# v7-flex2811_8x.net
KiCad netlist of a schematic drawn in EAGLE
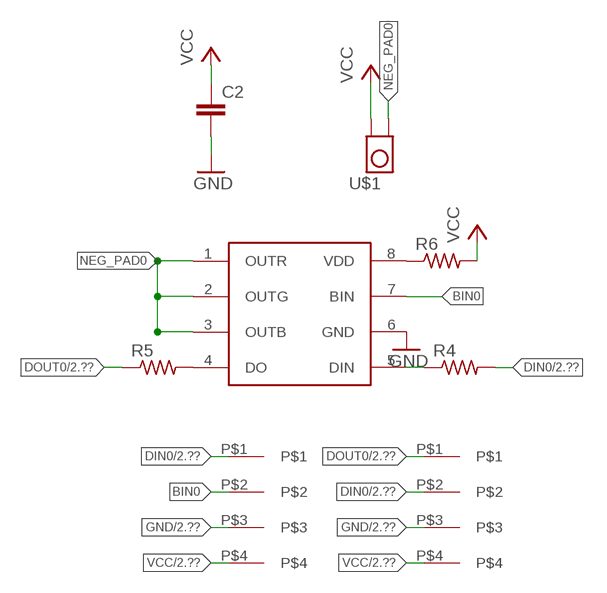
[diagram p0: schematic, sheet 1]
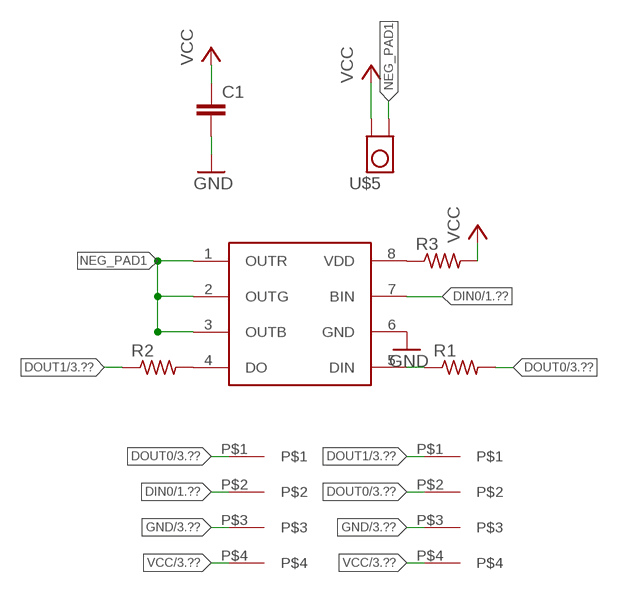
[diagram p1: schematic, sheet 2]
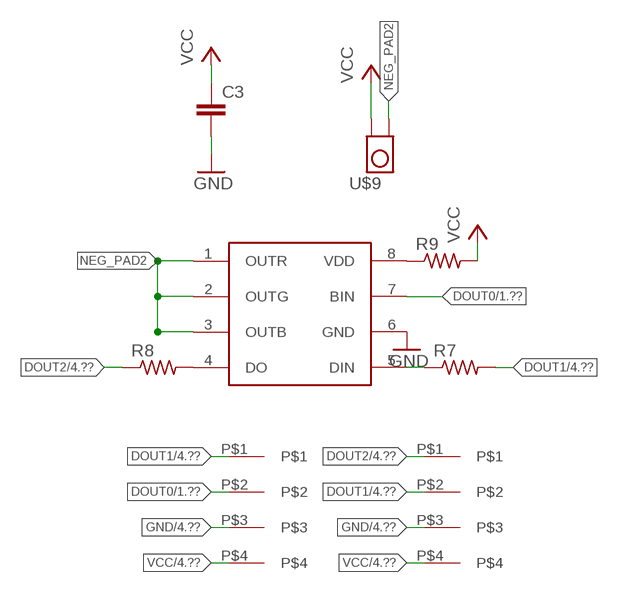
[diagram p2: schematic, sheet 3]
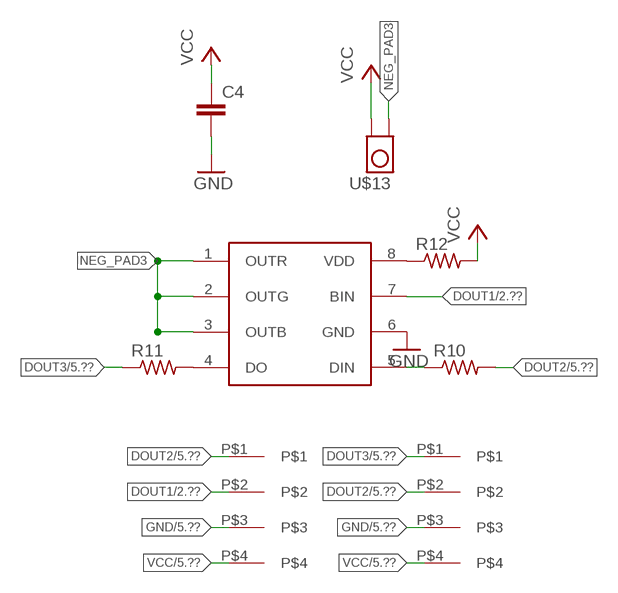
[diagram p3: schematic, sheet 4]
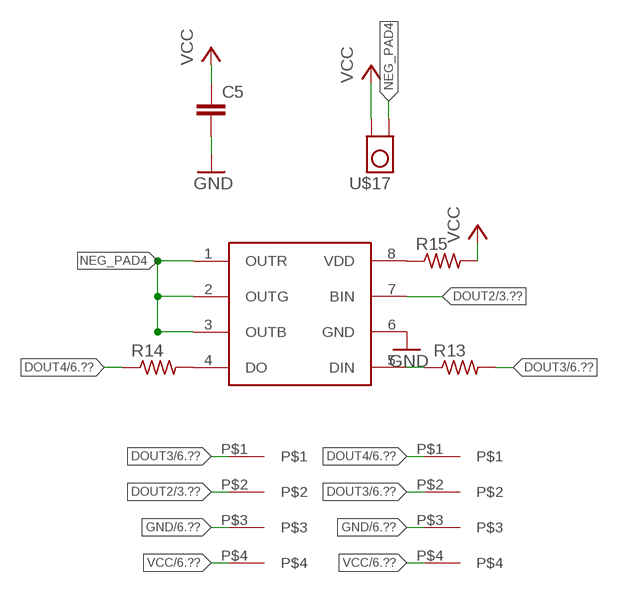
[diagram p4: schematic, sheet 5]
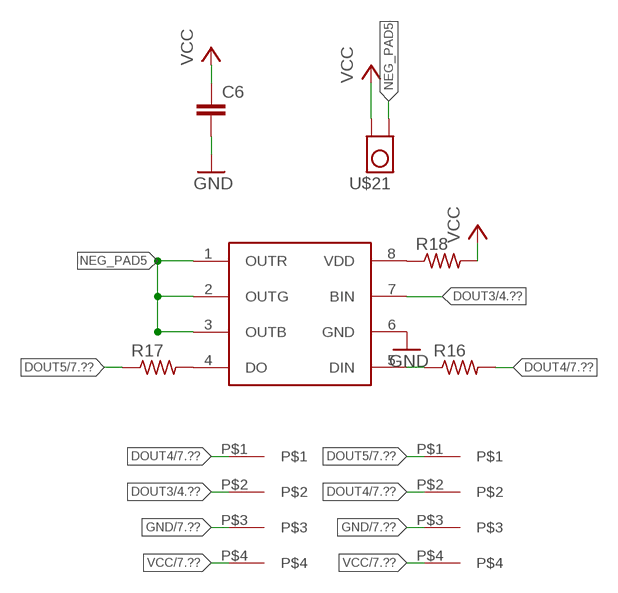
[diagram p5: schematic, sheet 6]
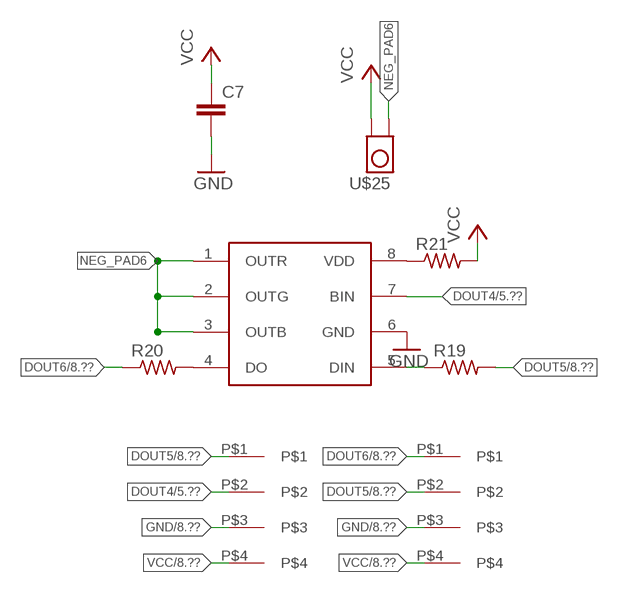
[diagram p6: schematic, sheet 7]
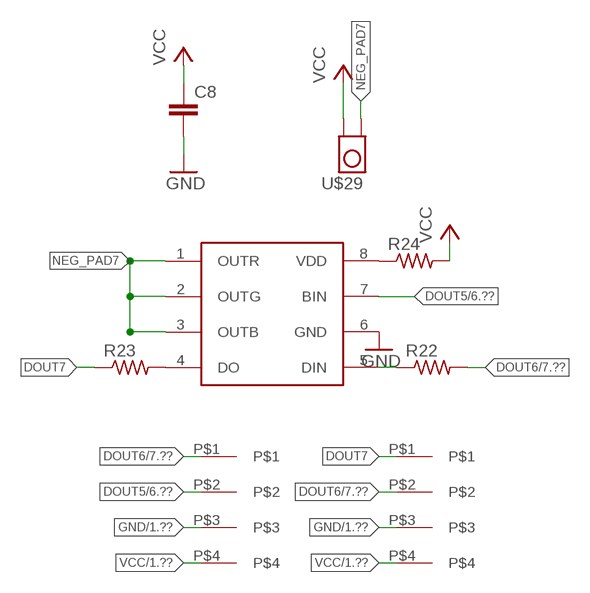
[diagram p7: schematic, sheet 8]

(export (version "E")
  (design (tool "Eeschema 10.0.6"))
  (components
    (comp (ref "C8")
      (value "C-EUC0201")
      (footprint "eagle-import:C0201")
      (libsource (lib "eagle-import") (part "C-EUC0201"))
    )
    (comp (ref "R22")
      (value "R-US_R0201")
      (footprint "eagle-import:R0201")
      (libsource (lib "eagle-import") (part "R-US_R0201"))
    )
    (comp (ref "R23")
      (value "R-US_R0201")
      (footprint "eagle-import:R0201")
      (libsource (lib "eagle-import") (part "R-US_R0201"))
    )
    (comp (ref "R24")
      (value "R-US_R0201")
      (footprint "eagle-import:R0201")
      (libsource (lib "eagle-import") (part "R-US_R0201"))
    )
    (comp (ref "U$29")
      (value "TP_4MM_MED_PAD")
      (footprint "eagle-import:TP_4MM_MED_PAD")
      (libsource (lib "eagle-import") (part "TP_4MM_MED_PAD"))
    )
    (comp (ref "U$30")
      (value "WS2818")
      (footprint "eagle-import:SO08")
      (libsource (lib "eagle-import") (part "WS2818"))
    )
    (comp (ref "U$31")
      (value "4PAD")
      (footprint "eagle-import:4PAD")
      (libsource (lib "eagle-import") (part "4PAD"))
    )
    (comp (ref "U$32")
      (value "4PAD")
      (footprint "eagle-import:4PAD")
      (libsource (lib "eagle-import") (part "4PAD"))
    )
    (comp (ref "C4")
      (value "C-EUC0201")
      (footprint "eagle-import:C0201")
      (libsource (lib "eagle-import") (part "C-EUC0201"))
    )
    (comp (ref "R10")
      (value "R-US_R0201")
      (footprint "eagle-import:R0201")
      (libsource (lib "eagle-import") (part "R-US_R0201"))
    )
    (comp (ref "R11")
      (value "R-US_R0201")
      (footprint "eagle-import:R0201")
      (libsource (lib "eagle-import") (part "R-US_R0201"))
    )
    (comp (ref "R12")
      (value "R-US_R0201")
      (footprint "eagle-import:R0201")
      (libsource (lib "eagle-import") (part "R-US_R0201"))
    )
    (comp (ref "U$13")
      (value "TP_4MM_MED_PAD")
      (footprint "eagle-import:TP_4MM_MED_PAD")
      (libsource (lib "eagle-import") (part "TP_4MM_MED_PAD"))
    )
    (comp (ref "U$14")
      (value "WS2818")
      (footprint "eagle-import:SO08")
      (libsource (lib "eagle-import") (part "WS2818"))
    )
    (comp (ref "U$15")
      (value "4PAD")
      (footprint "eagle-import:4PAD")
      (libsource (lib "eagle-import") (part "4PAD"))
    )
    (comp (ref "U$16")
      (value "4PAD")
      (footprint "eagle-import:4PAD")
      (libsource (lib "eagle-import") (part "4PAD"))
    )
    (comp (ref "C5")
      (value "C-EUC0201")
      (footprint "eagle-import:C0201")
      (libsource (lib "eagle-import") (part "C-EUC0201"))
    )
    (comp (ref "R13")
      (value "R-US_R0201")
      (footprint "eagle-import:R0201")
      (libsource (lib "eagle-import") (part "R-US_R0201"))
    )
    (comp (ref "R14")
      (value "R-US_R0201")
      (footprint "eagle-import:R0201")
      (libsource (lib "eagle-import") (part "R-US_R0201"))
    )
    (comp (ref "R15")
      (value "R-US_R0201")
      (footprint "eagle-import:R0201")
      (libsource (lib "eagle-import") (part "R-US_R0201"))
    )
    (comp (ref "U$17")
      (value "TP_4MM_MED_PAD")
      (footprint "eagle-import:TP_4MM_MED_PAD")
      (libsource (lib "eagle-import") (part "TP_4MM_MED_PAD"))
    )
    (comp (ref "U$18")
      (value "WS2818")
      (footprint "eagle-import:SO08")
      (libsource (lib "eagle-import") (part "WS2818"))
    )
    (comp (ref "U$19")
      (value "4PAD")
      (footprint "eagle-import:4PAD")
      (libsource (lib "eagle-import") (part "4PAD"))
    )
    (comp (ref "U$20")
      (value "4PAD")
      (footprint "eagle-import:4PAD")
      (libsource (lib "eagle-import") (part "4PAD"))
    )
    (comp (ref "C7")
      (value "C-EUC0201")
      (footprint "eagle-import:C0201")
      (libsource (lib "eagle-import") (part "C-EUC0201"))
    )
    (comp (ref "R19")
      (value "R-US_R0201")
      (footprint "eagle-import:R0201")
      (libsource (lib "eagle-import") (part "R-US_R0201"))
    )
    (comp (ref "R20")
      (value "R-US_R0201")
      (footprint "eagle-import:R0201")
      (libsource (lib "eagle-import") (part "R-US_R0201"))
    )
    (comp (ref "R21")
      (value "R-US_R0201")
      (footprint "eagle-import:R0201")
      (libsource (lib "eagle-import") (part "R-US_R0201"))
    )
    (comp (ref "U$25")
      (value "TP_4MM_MED_PAD")
      (footprint "eagle-import:TP_4MM_MED_PAD")
      (libsource (lib "eagle-import") (part "TP_4MM_MED_PAD"))
    )
    (comp (ref "U$26")
      (value "WS2818")
      (footprint "eagle-import:SO08")
      (libsource (lib "eagle-import") (part "WS2818"))
    )
    (comp (ref "U$27")
      (value "4PAD")
      (footprint "eagle-import:4PAD")
      (libsource (lib "eagle-import") (part "4PAD"))
    )
    (comp (ref "U$28")
      (value "4PAD")
      (footprint "eagle-import:4PAD")
      (libsource (lib "eagle-import") (part "4PAD"))
    )
    (comp (ref "C2")
      (value "C-EUC0201")
      (footprint "eagle-import:C0201")
      (libsource (lib "eagle-import") (part "C-EUC0201"))
    )
    (comp (ref "R4")
      (value "R-US_R0201")
      (footprint "eagle-import:R0201")
      (libsource (lib "eagle-import") (part "R-US_R0201"))
    )
    (comp (ref "R5")
      (value "R-US_R0201")
      (footprint "eagle-import:R0201")
      (libsource (lib "eagle-import") (part "R-US_R0201"))
    )
    (comp (ref "R6")
      (value "R-US_R0201")
      (footprint "eagle-import:R0201")
      (libsource (lib "eagle-import") (part "R-US_R0201"))
    )
    (comp (ref "U$1")
      (value "TP_4MM_MED_PAD")
      (footprint "eagle-import:TP_4MM_MED_PAD")
      (libsource (lib "eagle-import") (part "TP_4MM_MED_PAD"))
    )
    (comp (ref "U$2")
      (value "WS2818")
      (footprint "eagle-import:SO08")
      (libsource (lib "eagle-import") (part "WS2818"))
    )
    (comp (ref "U$3")
      (value "4PAD")
      (footprint "eagle-import:4PAD")
      (libsource (lib "eagle-import") (part "4PAD"))
    )
    (comp (ref "U$4")
      (value "4PAD")
      (footprint "eagle-import:4PAD")
      (libsource (lib "eagle-import") (part "4PAD"))
    )
    (comp (ref "C6")
      (value "C-EUC0201")
      (footprint "eagle-import:C0201")
      (libsource (lib "eagle-import") (part "C-EUC0201"))
    )
    (comp (ref "R16")
      (value "R-US_R0201")
      (footprint "eagle-import:R0201")
      (libsource (lib "eagle-import") (part "R-US_R0201"))
    )
    (comp (ref "R17")
      (value "R-US_R0201")
      (footprint "eagle-import:R0201")
      (libsource (lib "eagle-import") (part "R-US_R0201"))
    )
    (comp (ref "R18")
      (value "R-US_R0201")
      (footprint "eagle-import:R0201")
      (libsource (lib "eagle-import") (part "R-US_R0201"))
    )
    (comp (ref "U$21")
      (value "TP_4MM_MED_PAD")
      (footprint "eagle-import:TP_4MM_MED_PAD")
      (libsource (lib "eagle-import") (part "TP_4MM_MED_PAD"))
    )
    (comp (ref "U$22")
      (value "WS2818")
      (footprint "eagle-import:SO08")
      (libsource (lib "eagle-import") (part "WS2818"))
    )
    (comp (ref "U$23")
      (value "4PAD")
      (footprint "eagle-import:4PAD")
      (libsource (lib "eagle-import") (part "4PAD"))
    )
    (comp (ref "U$24")
      (value "4PAD")
      (footprint "eagle-import:4PAD")
      (libsource (lib "eagle-import") (part "4PAD"))
    )
    (comp (ref "C3")
      (value "C-EUC0201")
      (footprint "eagle-import:C0201")
      (libsource (lib "eagle-import") (part "C-EUC0201"))
    )
    (comp (ref "R7")
      (value "R-US_R0201")
      (footprint "eagle-import:R0201")
      (libsource (lib "eagle-import") (part "R-US_R0201"))
    )
    (comp (ref "R8")
      (value "R-US_R0201")
      (footprint "eagle-import:R0201")
      (libsource (lib "eagle-import") (part "R-US_R0201"))
    )
    (comp (ref "R9")
      (value "R-US_R0201")
      (footprint "eagle-import:R0201")
      (libsource (lib "eagle-import") (part "R-US_R0201"))
    )
    (comp (ref "U$9")
      (value "TP_4MM_MED_PAD")
      (footprint "eagle-import:TP_4MM_MED_PAD")
      (libsource (lib "eagle-import") (part "TP_4MM_MED_PAD"))
    )
    (comp (ref "U$10")
      (value "WS2818")
      (footprint "eagle-import:SO08")
      (libsource (lib "eagle-import") (part "WS2818"))
    )
    (comp (ref "U$11")
      (value "4PAD")
      (footprint "eagle-import:4PAD")
      (libsource (lib "eagle-import") (part "4PAD"))
    )
    (comp (ref "U$12")
      (value "4PAD")
      (footprint "eagle-import:4PAD")
      (libsource (lib "eagle-import") (part "4PAD"))
    )
    (comp (ref "C1")
      (value "C-EUC0201")
      (footprint "eagle-import:C0201")
      (libsource (lib "eagle-import") (part "C-EUC0201"))
    )
    (comp (ref "R1")
      (value "R-US_R0201")
      (footprint "eagle-import:R0201")
      (libsource (lib "eagle-import") (part "R-US_R0201"))
    )
    (comp (ref "R2")
      (value "R-US_R0201")
      (footprint "eagle-import:R0201")
      (libsource (lib "eagle-import") (part "R-US_R0201"))
    )
    (comp (ref "R3")
      (value "R-US_R0201")
      (footprint "eagle-import:R0201")
      (libsource (lib "eagle-import") (part "R-US_R0201"))
    )
    (comp (ref "U$5")
      (value "TP_4MM_MED_PAD")
      (footprint "eagle-import:TP_4MM_MED_PAD")
      (libsource (lib "eagle-import") (part "TP_4MM_MED_PAD"))
    )
    (comp (ref "U$6")
      (value "WS2818")
      (footprint "eagle-import:SO08")
      (libsource (lib "eagle-import") (part "WS2818"))
    )
    (comp (ref "U$7")
      (value "4PAD")
      (footprint "eagle-import:4PAD")
      (libsource (lib "eagle-import") (part "4PAD"))
    )
    (comp (ref "U$8")
      (value "4PAD")
      (footprint "eagle-import:4PAD")
      (libsource (lib "eagle-import") (part "4PAD"))
    )
  )
  (nets
    (net (code "1") (name "BIN0") (class "Default")
      (node (ref "U$2") (pin "7") (pinfunction "BIN_7") (pintype "bidirectional"))
      (node (ref "U$3") (pin "P$2") (pinfunction "P$2_P$2") (pintype "bidirectional"))
    )
    (net (code "2") (name "DIN0") (class "Default")
      (node (ref "R4") (pin "2") (pinfunction "2_2") (pintype "passive"))
      (node (ref "U$3") (pin "P$1") (pinfunction "P$1_P$1") (pintype "bidirectional"))
      (node (ref "U$4") (pin "P$2") (pinfunction "P$2_P$2") (pintype "bidirectional"))
      (node (ref "U$6") (pin "7") (pinfunction "BIN_7") (pintype "bidirectional"))
      (node (ref "U$7") (pin "P$2") (pinfunction "P$2_P$2") (pintype "bidirectional"))
    )
    (net (code "3") (name "DOUT0") (class "Default")
      (node (ref "R1") (pin "2") (pinfunction "2_2") (pintype "passive"))
      (node (ref "R5") (pin "1") (pinfunction "1_1") (pintype "passive"))
      (node (ref "U$10") (pin "7") (pinfunction "BIN_7") (pintype "bidirectional"))
      (node (ref "U$11") (pin "P$2") (pinfunction "P$2_P$2") (pintype "bidirectional"))
      (node (ref "U$4") (pin "P$1") (pinfunction "P$1_P$1") (pintype "bidirectional"))
      (node (ref "U$7") (pin "P$1") (pinfunction "P$1_P$1") (pintype "bidirectional"))
      (node (ref "U$8") (pin "P$2") (pinfunction "P$2_P$2") (pintype "bidirectional"))
    )
    (net (code "4") (name "DOUT1") (class "Default")
      (node (ref "R2") (pin "1") (pinfunction "1_1") (pintype "passive"))
      (node (ref "R7") (pin "2") (pinfunction "2_2") (pintype "passive"))
      (node (ref "U$11") (pin "P$1") (pinfunction "P$1_P$1") (pintype "bidirectional"))
      (node (ref "U$12") (pin "P$2") (pinfunction "P$2_P$2") (pintype "bidirectional"))
      (node (ref "U$14") (pin "7") (pinfunction "BIN_7") (pintype "bidirectional"))
      (node (ref "U$15") (pin "P$2") (pinfunction "P$2_P$2") (pintype "bidirectional"))
      (node (ref "U$8") (pin "P$1") (pinfunction "P$1_P$1") (pintype "bidirectional"))
    )
    (net (code "5") (name "DOUT2") (class "Default")
      (node (ref "R10") (pin "2") (pinfunction "2_2") (pintype "passive"))
      (node (ref "R8") (pin "1") (pinfunction "1_1") (pintype "passive"))
      (node (ref "U$12") (pin "P$1") (pinfunction "P$1_P$1") (pintype "bidirectional"))
      (node (ref "U$15") (pin "P$1") (pinfunction "P$1_P$1") (pintype "bidirectional"))
      (node (ref "U$16") (pin "P$2") (pinfunction "P$2_P$2") (pintype "bidirectional"))
      (node (ref "U$18") (pin "7") (pinfunction "BIN_7") (pintype "bidirectional"))
      (node (ref "U$19") (pin "P$2") (pinfunction "P$2_P$2") (pintype "bidirectional"))
    )
    (net (code "6") (name "DOUT3") (class "Default")
      (node (ref "R11") (pin "1") (pinfunction "1_1") (pintype "passive"))
      (node (ref "R13") (pin "2") (pinfunction "2_2") (pintype "passive"))
      (node (ref "U$16") (pin "P$1") (pinfunction "P$1_P$1") (pintype "bidirectional"))
      (node (ref "U$19") (pin "P$1") (pinfunction "P$1_P$1") (pintype "bidirectional"))
      (node (ref "U$20") (pin "P$2") (pinfunction "P$2_P$2") (pintype "bidirectional"))
      (node (ref "U$22") (pin "7") (pinfunction "BIN_7") (pintype "bidirectional"))
      (node (ref "U$23") (pin "P$2") (pinfunction "P$2_P$2") (pintype "bidirectional"))
    )
    (net (code "7") (name "DOUT4") (class "Default")
      (node (ref "R14") (pin "1") (pinfunction "1_1") (pintype "passive"))
      (node (ref "R16") (pin "2") (pinfunction "2_2") (pintype "passive"))
      (node (ref "U$20") (pin "P$1") (pinfunction "P$1_P$1") (pintype "bidirectional"))
      (node (ref "U$23") (pin "P$1") (pinfunction "P$1_P$1") (pintype "bidirectional"))
      (node (ref "U$24") (pin "P$2") (pinfunction "P$2_P$2") (pintype "bidirectional"))
      (node (ref "U$26") (pin "7") (pinfunction "BIN_7") (pintype "bidirectional"))
      (node (ref "U$27") (pin "P$2") (pinfunction "P$2_P$2") (pintype "bidirectional"))
    )
    (net (code "8") (name "DOUT5") (class "Default")
      (node (ref "R17") (pin "1") (pinfunction "1_1") (pintype "passive"))
      (node (ref "R19") (pin "2") (pinfunction "2_2") (pintype "passive"))
      (node (ref "U$24") (pin "P$1") (pinfunction "P$1_P$1") (pintype "bidirectional"))
      (node (ref "U$27") (pin "P$1") (pinfunction "P$1_P$1") (pintype "bidirectional"))
      (node (ref "U$28") (pin "P$2") (pinfunction "P$2_P$2") (pintype "bidirectional"))
      (node (ref "U$30") (pin "7") (pinfunction "BIN_7") (pintype "bidirectional"))
      (node (ref "U$31") (pin "P$2") (pinfunction "P$2_P$2") (pintype "bidirectional"))
    )
    (net (code "9") (name "DOUT6") (class "Default")
      (node (ref "R20") (pin "1") (pinfunction "1_1") (pintype "passive"))
      (node (ref "R22") (pin "2") (pinfunction "2_2") (pintype "passive"))
      (node (ref "U$28") (pin "P$1") (pinfunction "P$1_P$1") (pintype "bidirectional"))
      (node (ref "U$31") (pin "P$1") (pinfunction "P$1_P$1") (pintype "bidirectional"))
      (node (ref "U$32") (pin "P$2") (pinfunction "P$2_P$2") (pintype "bidirectional"))
    )
    (net (code "10") (name "DOUT7") (class "Default")
      (node (ref "R23") (pin "1") (pinfunction "1_1") (pintype "passive"))
      (node (ref "U$32") (pin "P$1") (pinfunction "P$1_P$1") (pintype "bidirectional"))
    )
    (net (code "11") (name "GND") (class "Default")
      (node (ref "C1") (pin "2") (pinfunction "2_2") (pintype "passive"))
      (node (ref "C2") (pin "2") (pinfunction "2_2") (pintype "passive"))
      (node (ref "C3") (pin "2") (pinfunction "2_2") (pintype "passive"))
      (node (ref "C4") (pin "2") (pinfunction "2_2") (pintype "passive"))
      (node (ref "C5") (pin "2") (pinfunction "2_2") (pintype "passive"))
      (node (ref "C6") (pin "2") (pinfunction "2_2") (pintype "passive"))
      (node (ref "C7") (pin "2") (pinfunction "2_2") (pintype "passive"))
      (node (ref "C8") (pin "2") (pinfunction "2_2") (pintype "passive"))
      (node (ref "U$10") (pin "6") (pinfunction "GND_6") (pintype "bidirectional"))
      (node (ref "U$11") (pin "P$3") (pinfunction "P$3_P$3") (pintype "bidirectional"))
      (node (ref "U$12") (pin "P$3") (pinfunction "P$3_P$3") (pintype "bidirectional"))
      (node (ref "U$14") (pin "6") (pinfunction "GND_6") (pintype "bidirectional"))
      (node (ref "U$15") (pin "P$3") (pinfunction "P$3_P$3") (pintype "bidirectional"))
      (node (ref "U$16") (pin "P$3") (pinfunction "P$3_P$3") (pintype "bidirectional"))
      (node (ref "U$18") (pin "6") (pinfunction "GND_6") (pintype "bidirectional"))
      (node (ref "U$19") (pin "P$3") (pinfunction "P$3_P$3") (pintype "bidirectional"))
      (node (ref "U$2") (pin "6") (pinfunction "GND_6") (pintype "bidirectional"))
      (node (ref "U$20") (pin "P$3") (pinfunction "P$3_P$3") (pintype "bidirectional"))
      (node (ref "U$22") (pin "6") (pinfunction "GND_6") (pintype "bidirectional"))
      (node (ref "U$23") (pin "P$3") (pinfunction "P$3_P$3") (pintype "bidirectional"))
      (node (ref "U$24") (pin "P$3") (pinfunction "P$3_P$3") (pintype "bidirectional"))
      (node (ref "U$26") (pin "6") (pinfunction "GND_6") (pintype "bidirectional"))
      (node (ref "U$27") (pin "P$3") (pinfunction "P$3_P$3") (pintype "bidirectional"))
      (node (ref "U$28") (pin "P$3") (pinfunction "P$3_P$3") (pintype "bidirectional"))
      (node (ref "U$3") (pin "P$3") (pinfunction "P$3_P$3") (pintype "bidirectional"))
      (node (ref "U$30") (pin "6") (pinfunction "GND_6") (pintype "bidirectional"))
      (node (ref "U$31") (pin "P$3") (pinfunction "P$3_P$3") (pintype "bidirectional"))
      (node (ref "U$32") (pin "P$3") (pinfunction "P$3_P$3") (pintype "bidirectional"))
      (node (ref "U$4") (pin "P$3") (pinfunction "P$3_P$3") (pintype "bidirectional"))
      (node (ref "U$6") (pin "6") (pinfunction "GND_6") (pintype "bidirectional"))
      (node (ref "U$7") (pin "P$3") (pinfunction "P$3_P$3") (pintype "bidirectional"))
      (node (ref "U$8") (pin "P$3") (pinfunction "P$3_P$3") (pintype "bidirectional"))
    )
    (net (code "12") (name "NEG_PAD0") (class "Default")
      (node (ref "U$1") (pin "P$1") (pinfunction "0_P$1") (pintype "bidirectional"))
      (node (ref "U$2") (pin "1") (pinfunction "OUTR_1") (pintype "bidirectional"))
      (node (ref "U$2") (pin "2") (pinfunction "OUTG_2") (pintype "bidirectional"))
      (node (ref "U$2") (pin "3") (pinfunction "OUTB_3") (pintype "bidirectional"))
    )
    (net (code "13") (name "NEG_PAD1") (class "Default")
      (node (ref "U$5") (pin "P$1") (pinfunction "0_P$1") (pintype "bidirectional"))
      (node (ref "U$6") (pin "1") (pinfunction "OUTR_1") (pintype "bidirectional"))
      (node (ref "U$6") (pin "2") (pinfunction "OUTG_2") (pintype "bidirectional"))
      (node (ref "U$6") (pin "3") (pinfunction "OUTB_3") (pintype "bidirectional"))
    )
    (net (code "14") (name "NEG_PAD2") (class "Default")
      (node (ref "U$10") (pin "1") (pinfunction "OUTR_1") (pintype "bidirectional"))
      (node (ref "U$10") (pin "2") (pinfunction "OUTG_2") (pintype "bidirectional"))
      (node (ref "U$10") (pin "3") (pinfunction "OUTB_3") (pintype "bidirectional"))
      (node (ref "U$9") (pin "P$1") (pinfunction "0_P$1") (pintype "bidirectional"))
    )
    (net (code "15") (name "NEG_PAD3") (class "Default")
      (node (ref "U$13") (pin "P$1") (pinfunction "0_P$1") (pintype "bidirectional"))
      (node (ref "U$14") (pin "1") (pinfunction "OUTR_1") (pintype "bidirectional"))
      (node (ref "U$14") (pin "2") (pinfunction "OUTG_2") (pintype "bidirectional"))
      (node (ref "U$14") (pin "3") (pinfunction "OUTB_3") (pintype "bidirectional"))
    )
    (net (code "16") (name "NEG_PAD4") (class "Default")
      (node (ref "U$17") (pin "P$1") (pinfunction "0_P$1") (pintype "bidirectional"))
      (node (ref "U$18") (pin "1") (pinfunction "OUTR_1") (pintype "bidirectional"))
      (node (ref "U$18") (pin "2") (pinfunction "OUTG_2") (pintype "bidirectional"))
      (node (ref "U$18") (pin "3") (pinfunction "OUTB_3") (pintype "bidirectional"))
    )
    (net (code "17") (name "NEG_PAD5") (class "Default")
      (node (ref "U$21") (pin "P$1") (pinfunction "0_P$1") (pintype "bidirectional"))
      (node (ref "U$22") (pin "1") (pinfunction "OUTR_1") (pintype "bidirectional"))
      (node (ref "U$22") (pin "2") (pinfunction "OUTG_2") (pintype "bidirectional"))
      (node (ref "U$22") (pin "3") (pinfunction "OUTB_3") (pintype "bidirectional"))
    )
    (net (code "18") (name "NEG_PAD6") (class "Default")
      (node (ref "U$25") (pin "P$1") (pinfunction "0_P$1") (pintype "bidirectional"))
      (node (ref "U$26") (pin "1") (pinfunction "OUTR_1") (pintype "bidirectional"))
      (node (ref "U$26") (pin "2") (pinfunction "OUTG_2") (pintype "bidirectional"))
      (node (ref "U$26") (pin "3") (pinfunction "OUTB_3") (pintype "bidirectional"))
    )
    (net (code "19") (name "NEG_PAD7") (class "Default")
      (node (ref "U$29") (pin "P$1") (pinfunction "0_P$1") (pintype "bidirectional"))
      (node (ref "U$30") (pin "1") (pinfunction "OUTR_1") (pintype "bidirectional"))
      (node (ref "U$30") (pin "2") (pinfunction "OUTG_2") (pintype "bidirectional"))
      (node (ref "U$30") (pin "3") (pinfunction "OUTB_3") (pintype "bidirectional"))
    )
    (net (code "20") (name "Net-(U$2-DIN)") (class "Default")
      (node (ref "R4") (pin "1") (pinfunction "1_1") (pintype "passive"))
      (node (ref "U$2") (pin "5") (pinfunction "DIN_5") (pintype "bidirectional"))
    )
    (net (code "21") (name "Net-(U$2-DO)") (class "Default")
      (node (ref "R5") (pin "2") (pinfunction "2_2") (pintype "passive"))
      (node (ref "U$2") (pin "4") (pinfunction "DO_4") (pintype "bidirectional"))
    )
    (net (code "22") (name "Net-(U$2-VDD)") (class "Default")
      (node (ref "R6") (pin "1") (pinfunction "1_1") (pintype "passive"))
      (node (ref "U$2") (pin "8") (pinfunction "VDD_8") (pintype "bidirectional"))
    )
    (net (code "23") (name "Net-(U$6-DIN)") (class "Default")
      (node (ref "R1") (pin "1") (pinfunction "1_1") (pintype "passive"))
      (node (ref "U$6") (pin "5") (pinfunction "DIN_5") (pintype "bidirectional"))
    )
    (net (code "24") (name "Net-(U$6-DO)") (class "Default")
      (node (ref "R2") (pin "2") (pinfunction "2_2") (pintype "passive"))
      (node (ref "U$6") (pin "4") (pinfunction "DO_4") (pintype "bidirectional"))
    )
    (net (code "25") (name "Net-(U$6-VDD)") (class "Default")
      (node (ref "R3") (pin "1") (pinfunction "1_1") (pintype "passive"))
      (node (ref "U$6") (pin "8") (pinfunction "VDD_8") (pintype "bidirectional"))
    )
    (net (code "26") (name "Net-(U$10-DIN)") (class "Default")
      (node (ref "R7") (pin "1") (pinfunction "1_1") (pintype "passive"))
      (node (ref "U$10") (pin "5") (pinfunction "DIN_5") (pintype "bidirectional"))
    )
    (net (code "27") (name "Net-(U$10-DO)") (class "Default")
      (node (ref "R8") (pin "2") (pinfunction "2_2") (pintype "passive"))
      (node (ref "U$10") (pin "4") (pinfunction "DO_4") (pintype "bidirectional"))
    )
    (net (code "28") (name "Net-(U$10-VDD)") (class "Default")
      (node (ref "R9") (pin "1") (pinfunction "1_1") (pintype "passive"))
      (node (ref "U$10") (pin "8") (pinfunction "VDD_8") (pintype "bidirectional"))
    )
    (net (code "29") (name "Net-(U$14-DIN)") (class "Default")
      (node (ref "R10") (pin "1") (pinfunction "1_1") (pintype "passive"))
      (node (ref "U$14") (pin "5") (pinfunction "DIN_5") (pintype "bidirectional"))
    )
    (net (code "30") (name "Net-(U$14-DO)") (class "Default")
      (node (ref "R11") (pin "2") (pinfunction "2_2") (pintype "passive"))
      (node (ref "U$14") (pin "4") (pinfunction "DO_4") (pintype "bidirectional"))
    )
    (net (code "31") (name "Net-(U$14-VDD)") (class "Default")
      (node (ref "R12") (pin "1") (pinfunction "1_1") (pintype "passive"))
      (node (ref "U$14") (pin "8") (pinfunction "VDD_8") (pintype "bidirectional"))
    )
    (net (code "32") (name "Net-(U$18-DIN)") (class "Default")
      (node (ref "R13") (pin "1") (pinfunction "1_1") (pintype "passive"))
      (node (ref "U$18") (pin "5") (pinfunction "DIN_5") (pintype "bidirectional"))
    )
    (net (code "33") (name "Net-(U$18-DO)") (class "Default")
      (node (ref "R14") (pin "2") (pinfunction "2_2") (pintype "passive"))
      (node (ref "U$18") (pin "4") (pinfunction "DO_4") (pintype "bidirectional"))
    )
    (net (code "34") (name "Net-(U$18-VDD)") (class "Default")
      (node (ref "R15") (pin "1") (pinfunction "1_1") (pintype "passive"))
      (node (ref "U$18") (pin "8") (pinfunction "VDD_8") (pintype "bidirectional"))
    )
    (net (code "35") (name "Net-(U$22-DIN)") (class "Default")
      (node (ref "R16") (pin "1") (pinfunction "1_1") (pintype "passive"))
      (node (ref "U$22") (pin "5") (pinfunction "DIN_5") (pintype "bidirectional"))
    )
    (net (code "36") (name "Net-(U$22-DO)") (class "Default")
      (node (ref "R17") (pin "2") (pinfunction "2_2") (pintype "passive"))
      (node (ref "U$22") (pin "4") (pinfunction "DO_4") (pintype "bidirectional"))
    )
    (net (code "37") (name "Net-(U$22-VDD)") (class "Default")
      (node (ref "R18") (pin "1") (pinfunction "1_1") (pintype "passive"))
      (node (ref "U$22") (pin "8") (pinfunction "VDD_8") (pintype "bidirectional"))
    )
    (net (code "38") (name "Net-(U$26-DIN)") (class "Default")
      (node (ref "R19") (pin "1") (pinfunction "1_1") (pintype "passive"))
      (node (ref "U$26") (pin "5") (pinfunction "DIN_5") (pintype "bidirectional"))
    )
    (net (code "39") (name "Net-(U$26-DO)") (class "Default")
      (node (ref "R20") (pin "2") (pinfunction "2_2") (pintype "passive"))
      (node (ref "U$26") (pin "4") (pinfunction "DO_4") (pintype "bidirectional"))
    )
    (net (code "40") (name "Net-(U$26-VDD)") (class "Default")
      (node (ref "R21") (pin "1") (pinfunction "1_1") (pintype "passive"))
      (node (ref "U$26") (pin "8") (pinfunction "VDD_8") (pintype "bidirectional"))
    )
    (net (code "41") (name "Net-(U$30-DIN)") (class "Default")
      (node (ref "R22") (pin "1") (pinfunction "1_1") (pintype "passive"))
      (node (ref "U$30") (pin "5") (pinfunction "DIN_5") (pintype "bidirectional"))
    )
    (net (code "42") (name "Net-(U$30-DO)") (class "Default")
      (node (ref "R23") (pin "2") (pinfunction "2_2") (pintype "passive"))
      (node (ref "U$30") (pin "4") (pinfunction "DO_4") (pintype "bidirectional"))
    )
    (net (code "43") (name "Net-(U$30-VDD)") (class "Default")
      (node (ref "R24") (pin "1") (pinfunction "1_1") (pintype "passive"))
      (node (ref "U$30") (pin "8") (pinfunction "VDD_8") (pintype "bidirectional"))
    )
    (net (code "44") (name "VCC") (class "Default")
      (node (ref "C1") (pin "1") (pinfunction "1_1") (pintype "passive"))
      (node (ref "C2") (pin "1") (pinfunction "1_1") (pintype "passive"))
      (node (ref "C3") (pin "1") (pinfunction "1_1") (pintype "passive"))
      (node (ref "C4") (pin "1") (pinfunction "1_1") (pintype "passive"))
      (node (ref "C5") (pin "1") (pinfunction "1_1") (pintype "passive"))
      (node (ref "C6") (pin "1") (pinfunction "1_1") (pintype "passive"))
      (node (ref "C7") (pin "1") (pinfunction "1_1") (pintype "passive"))
      (node (ref "C8") (pin "1") (pinfunction "1_1") (pintype "passive"))
      (node (ref "R12") (pin "2") (pinfunction "2_2") (pintype "passive"))
      (node (ref "R15") (pin "2") (pinfunction "2_2") (pintype "passive"))
      (node (ref "R18") (pin "2") (pinfunction "2_2") (pintype "passive"))
      (node (ref "R21") (pin "2") (pinfunction "2_2") (pintype "passive"))
      (node (ref "R24") (pin "2") (pinfunction "2_2") (pintype "passive"))
      (node (ref "R3") (pin "2") (pinfunction "2_2") (pintype "passive"))
      (node (ref "R6") (pin "2") (pinfunction "2_2") (pintype "passive"))
      (node (ref "R9") (pin "2") (pinfunction "2_2") (pintype "passive"))
      (node (ref "U$1") (pin "P$2") (pinfunction "1_P$2") (pintype "bidirectional"))
      (node (ref "U$11") (pin "P$4") (pinfunction "P$4_P$4") (pintype "bidirectional"))
      (node (ref "U$12") (pin "P$4") (pinfunction "P$4_P$4") (pintype "bidirectional"))
      (node (ref "U$13") (pin "P$2") (pinfunction "1_P$2") (pintype "bidirectional"))
      (node (ref "U$15") (pin "P$4") (pinfunction "P$4_P$4") (pintype "bidirectional"))
      (node (ref "U$16") (pin "P$4") (pinfunction "P$4_P$4") (pintype "bidirectional"))
      (node (ref "U$17") (pin "P$2") (pinfunction "1_P$2") (pintype "bidirectional"))
      (node (ref "U$19") (pin "P$4") (pinfunction "P$4_P$4") (pintype "bidirectional"))
      (node (ref "U$20") (pin "P$4") (pinfunction "P$4_P$4") (pintype "bidirectional"))
      (node (ref "U$21") (pin "P$2") (pinfunction "1_P$2") (pintype "bidirectional"))
      (node (ref "U$23") (pin "P$4") (pinfunction "P$4_P$4") (pintype "bidirectional"))
      (node (ref "U$24") (pin "P$4") (pinfunction "P$4_P$4") (pintype "bidirectional"))
      (node (ref "U$25") (pin "P$2") (pinfunction "1_P$2") (pintype "bidirectional"))
      (node (ref "U$27") (pin "P$4") (pinfunction "P$4_P$4") (pintype "bidirectional"))
      (node (ref "U$28") (pin "P$4") (pinfunction "P$4_P$4") (pintype "bidirectional"))
      (node (ref "U$29") (pin "P$2") (pinfunction "1_P$2") (pintype "bidirectional"))
      (node (ref "U$3") (pin "P$4") (pinfunction "P$4_P$4") (pintype "bidirectional"))
      (node (ref "U$31") (pin "P$4") (pinfunction "P$4_P$4") (pintype "bidirectional"))
      (node (ref "U$32") (pin "P$4") (pinfunction "P$4_P$4") (pintype "bidirectional"))
      (node (ref "U$4") (pin "P$4") (pinfunction "P$4_P$4") (pintype "bidirectional"))
      (node (ref "U$5") (pin "P$2") (pinfunction "1_P$2") (pintype "bidirectional"))
      (node (ref "U$7") (pin "P$4") (pinfunction "P$4_P$4") (pintype "bidirectional"))
      (node (ref "U$8") (pin "P$4") (pinfunction "P$4_P$4") (pintype "bidirectional"))
      (node (ref "U$9") (pin "P$2") (pinfunction "1_P$2") (pintype "bidirectional"))
    )
  )
)
